# BOB_v1_04.net
KiCad netlist of a schematic drawn in EAGLE
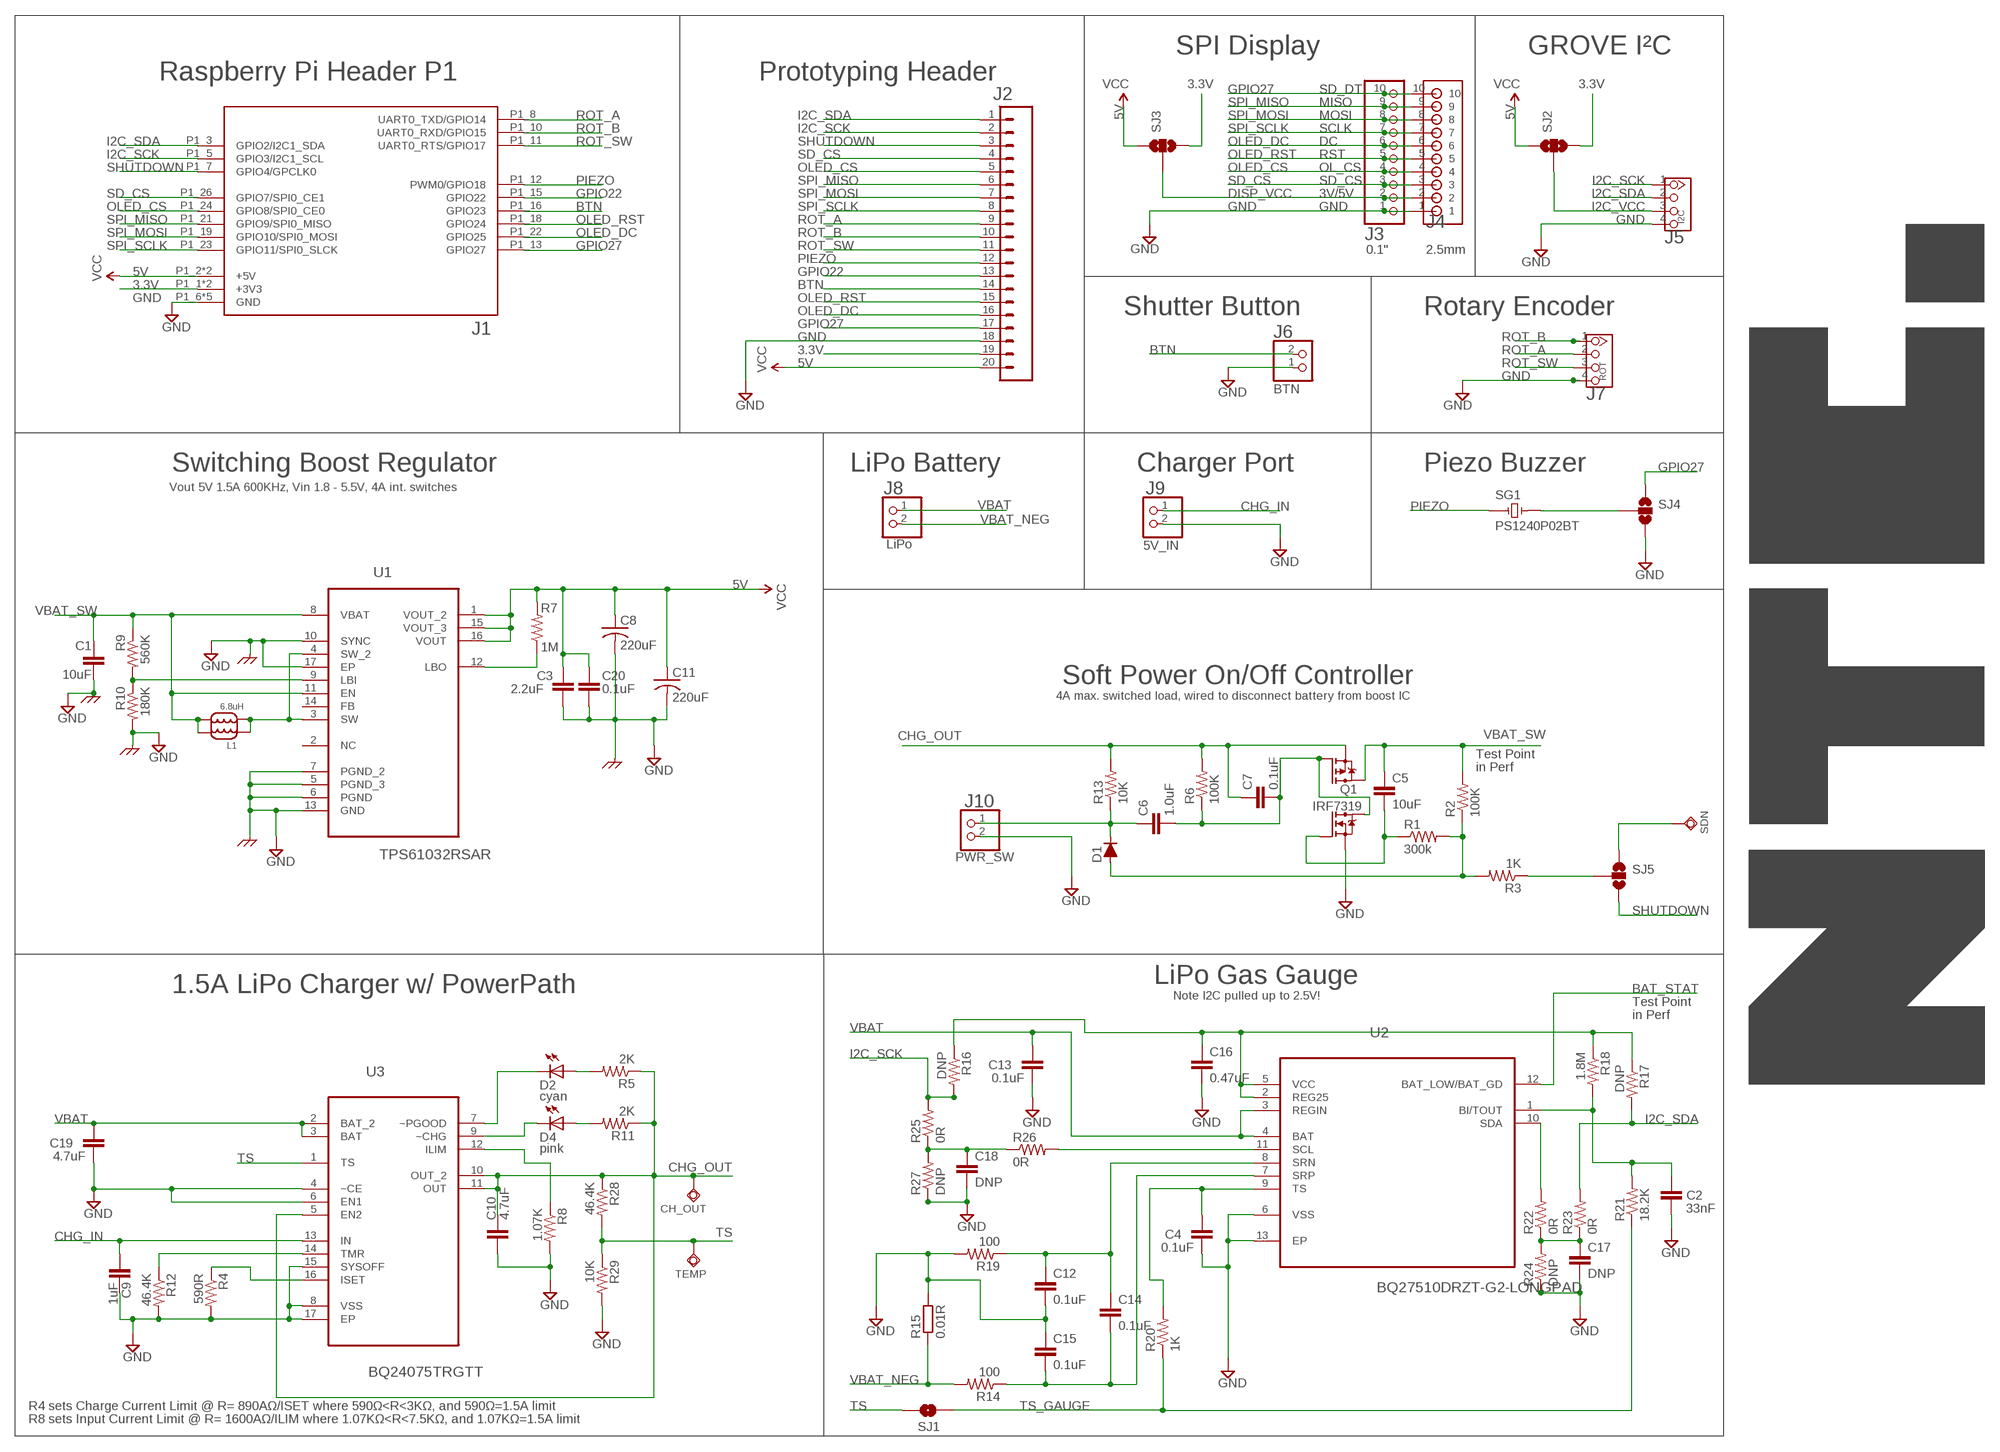
[diagram p0: schematic, sheet 1]

(export (version "E")
  (design (tool "Eeschema 10.0.6"))
  (components
    (comp (ref "C1")
      (value "10uF")
      (footprint "eagle-import:1206")
      (libsource (lib "eagle-import") (part "CAP1206"))
    )
    (comp (ref "C2")
      (value "33nF")
      (footprint "eagle-import:0603-CAP")
      (libsource (lib "eagle-import") (part "CAP0603-CAP"))
    )
    (comp (ref "C3")
      (value "2.2uF")
      (footprint "eagle-import:0603")
      (libsource (lib "eagle-import") (part "CAP0603"))
    )
    (comp (ref "C4")
      (value "0.1uF")
      (footprint "eagle-import:0603-CAP")
      (libsource (lib "eagle-import") (part "CAP0603-CAP"))
    )
    (comp (ref "C5")
      (value "10uF")
      (footprint "eagle-import:0603-CAP")
      (libsource (lib "eagle-import") (part "10UF-6.3V-20%(0603)"))
    )
    (comp (ref "C6")
      (value "1.0uF")
      (footprint "eagle-import:0603-CAP")
      (libsource (lib "eagle-import") (part "1.0UF-16V-10%(0603)"))
    )
    (comp (ref "C7")
      (value "0.1uF")
      (footprint "eagle-import:0603-CAP")
      (libsource (lib "eagle-import") (part "0.1UF-25V-5%(0603)"))
    )
    (comp (ref "C8")
      (value "220uF")
      (footprint "eagle-import:C1210")
      (libsource (lib "eagle-import") (part "C-USC1210"))
    )
    (comp (ref "C9")
      (value "1uF")
      (footprint "eagle-import:0603-CAP")
      (libsource (lib "eagle-import") (part "CAP0603-CAP"))
    )
    (comp (ref "C10")
      (value "4.7uF")
      (footprint "eagle-import:0603-CAP")
      (libsource (lib "eagle-import") (part "CAP0603-CAP"))
    )
    (comp (ref "C11")
      (value "220uF")
      (footprint "eagle-import:C1210")
      (libsource (lib "eagle-import") (part "C-USC1210"))
    )
    (comp (ref "C12")
      (value "0.1uF")
      (footprint "eagle-import:0603-CAP")
      (libsource (lib "eagle-import") (part "SparkFun-Capacitors_CAP0603-CAP"))
    )
    (comp (ref "C13")
      (value "0.1uF")
      (footprint "eagle-import:0603-CAP")
      (libsource (lib "eagle-import") (part "CAP0603-CAP"))
    )
    (comp (ref "C14")
      (value "0.1uF")
      (footprint "eagle-import:0603-CAP")
      (libsource (lib "eagle-import") (part "SparkFun-Capacitors_CAP0603-CAP"))
    )
    (comp (ref "C15")
      (value "0.1uF")
      (footprint "eagle-import:0603-CAP")
      (libsource (lib "eagle-import") (part "SparkFun-Capacitors_CAP0603-CAP"))
    )
    (comp (ref "C16")
      (value "0.47uF")
      (footprint "eagle-import:0603-CAP")
      (libsource (lib "eagle-import") (part "SparkFun-Capacitors_CAP0603-CAP"))
    )
    (comp (ref "C17")
      (value "DNP")
      (footprint "eagle-import:0603-CAP")
      (libsource (lib "eagle-import") (part "SparkFun-Capacitors_CAP0603-CAP"))
    )
    (comp (ref "C18")
      (value "DNP")
      (footprint "eagle-import:0603-CAP")
      (libsource (lib "eagle-import") (part "SparkFun-Capacitors_CAP0603-CAP"))
    )
    (comp (ref "C19")
      (value "4.7uF")
      (footprint "eagle-import:0603-CAP")
      (libsource (lib "eagle-import") (part "CAP0603-CAP"))
    )
    (comp (ref "C20")
      (value "0.1uF")
      (footprint "eagle-import:0603-CAP")
      (fields (field (name "PROD_ID") "CAP-00868"))
      (libsource (lib "eagle-import") (part "1.0UF-16V-10%(0603)"))
    )
    (comp (ref "CH_OUT")
      (value "TP1.2")
      (footprint "eagle-import:TP_1.2")
      (libsource (lib "eagle-import") (part "TP1.2"))
    )
    (comp (ref "D1")
      (value "D-FILL-SMB")
      (footprint "eagle-import:SMB")
      (libsource (lib "eagle-import") (part "D-FILL-SMB"))
    )
    (comp (ref "D2")
      (value "cyan")
      (footprint "eagle-import:LED-0603")
      (libsource (lib "eagle-import") (part "LED0603"))
    )
    (comp (ref "D4")
      (value "pink")
      (footprint "eagle-import:LED-0603")
      (libsource (lib "eagle-import") (part "LED0603"))
    )
    (comp (ref "J1")
      (value "PICAM_RPI-B-PICAM")
      (footprint "eagle-import:PICAM_RPI-B-PICAM")
      (libsource (lib "eagle-import") (part "PICAM_RPI-B-PICAM"))
    )
    (comp (ref "J2")
      (value "M20LOCK_LONGPADS")
      (footprint "eagle-import:1X20_LOCK_LONGPADS")
      (libsource (lib "eagle-import") (part "M20LOCK_LONGPADS"))
    )
    (comp (ref "J3")
      (value "PINHD-1X10")
      (footprint "eagle-import:1X10-BIG")
      (libsource (lib "eagle-import") (part "PINHD-1X10"))
    )
    (comp (ref "J4")
      (value "B10B-EH-A-RA")
      (footprint "eagle-import:S10B-EH")
      (libsource (lib "eagle-import") (part "B10B-EH-A-RA"))
    )
    (comp (ref "J5")
      (value "I2C")
      (footprint "eagle-import:CONNECTOR_4P-2.0-REVGND")
      (libsource (lib "eagle-import") (part "CONNECTOR_TWIG-4P-2.0"))
    )
    (comp (ref "J6")
      (value "BTN")
      (footprint "eagle-import:JST-PH-2-THM-REVGND")
      (libsource (lib "eagle-import") (part "JST_2PIN"))
    )
    (comp (ref "J7")
      (value "ROT")
      (footprint "eagle-import:CONNECTOR_4P-2.0-REVGND")
      (libsource (lib "eagle-import") (part "CONNECTOR_TWIG-4P-2.0"))
    )
    (comp (ref "J8")
      (value "LiPo")
      (footprint "eagle-import:PICAM_JST-PH-2-THM")
      (libsource (lib "eagle-import") (part "PICAM_JST_2PIN-THM"))
    )
    (comp (ref "J9")
      (value "5V_IN")
      (footprint "eagle-import:PICAM_JST-PH-2-THM")
      (libsource (lib "eagle-import") (part "PICAM_JST_2PIN-THM"))
    )
    (comp (ref "J10")
      (value "PWR_SW")
      (footprint "eagle-import:PICAM_JST-PH-2-THM")
      (libsource (lib "eagle-import") (part "PICAM_JST_2PIN-THM"))
    )
    (comp (ref "L1")
      (value "6.8uH")
      (footprint "eagle-import:SUMIDA_CDRH124")
      (libsource (lib "eagle-import") (part "SUMIDA_CDRH124CDRH124NP-6R8MC"))
    )
    (comp (ref "Q1")
      (value "IRF7319")
      (footprint "eagle-import:SO08-IRF")
      (libsource (lib "eagle-import") (part "IRF7319Q"))
    )
    (comp (ref "R1")
      (value "300k")
      (footprint "eagle-import:0603-RES")
      (libsource (lib "eagle-import") (part "SparkFun-Passives_RESISTOR0603-RES"))
    )
    (comp (ref "R2")
      (value "100K")
      (footprint "eagle-import:0603-RES")
      (libsource (lib "eagle-import") (part "SparkFun-Passives_RESISTOR0603-RES"))
    )
    (comp (ref "R3")
      (value "1K")
      (footprint "eagle-import:0603-RES")
      (libsource (lib "eagle-import") (part "SparkFun-Passives_RESISTOR0603-RES"))
    )
    (comp (ref "R4")
      (value "590R")
      (footprint "eagle-import:0603-RES")
      (libsource (lib "eagle-import") (part "RESISTOR0603-RES"))
    )
    (comp (ref "R5")
      (value "2K")
      (footprint "eagle-import:0603-RES")
      (libsource (lib "eagle-import") (part "RESISTOR0603-RES"))
    )
    (comp (ref "R6")
      (value "100K")
      (footprint "eagle-import:0603-RES")
      (libsource (lib "eagle-import") (part "SparkFun-Passives_RESISTOR0603-RES"))
    )
    (comp (ref "R7")
      (value "1M")
      (footprint "eagle-import:0603-RES")
      (libsource (lib "eagle-import") (part "RESISTOR0603-RES"))
    )
    (comp (ref "R8")
      (value "1.07K")
      (footprint "eagle-import:0603-RES")
      (libsource (lib "eagle-import") (part "RESISTOR0603-RES"))
    )
    (comp (ref "R9")
      (value "560K")
      (footprint "eagle-import:0603-RES")
      (libsource (lib "eagle-import") (part "RESISTOR0603-RES"))
    )
    (comp (ref "R10")
      (value "180K")
      (footprint "eagle-import:0603-RES")
      (libsource (lib "eagle-import") (part "RESISTOR0603-RES"))
    )
    (comp (ref "R11")
      (value "2K")
      (footprint "eagle-import:0603-RES")
      (libsource (lib "eagle-import") (part "RESISTOR0603-RES"))
    )
    (comp (ref "R12")
      (value "46.4K")
      (footprint "eagle-import:0603-RES")
      (libsource (lib "eagle-import") (part "RESISTOR0603-RES"))
    )
    (comp (ref "R13")
      (value "10K")
      (footprint "eagle-import:0603-RES")
      (libsource (lib "eagle-import") (part "SparkFun-Passives_RESISTOR0603-RES"))
    )
    (comp (ref "R14")
      (value "100")
      (footprint "eagle-import:0603-RES")
      (libsource (lib "eagle-import") (part "RESISTOR0603-RES"))
    )
    (comp (ref "R15")
      (value "0.01R")
      (footprint "eagle-import:R1206")
      (libsource (lib "eagle-import") (part "RESISTOR-1206"))
    )
    (comp (ref "R16")
      (value "DNP")
      (footprint "eagle-import:0603-RES")
      (libsource (lib "eagle-import") (part "RESISTOR0603-RES"))
    )
    (comp (ref "R17")
      (value "DNP")
      (footprint "eagle-import:0603-RES")
      (libsource (lib "eagle-import") (part "RESISTOR0603-RES"))
    )
    (comp (ref "R18")
      (value "1.8M")
      (footprint "eagle-import:0603-RES")
      (libsource (lib "eagle-import") (part "RESISTOR0603-RES"))
    )
    (comp (ref "R19")
      (value "100")
      (footprint "eagle-import:0603-RES")
      (libsource (lib "eagle-import") (part "RESISTOR0603-RES"))
    )
    (comp (ref "R20")
      (value "1K")
      (footprint "eagle-import:0603-RES")
      (libsource (lib "eagle-import") (part "SparkFun-Resistors_RESISTOR0603-RES"))
    )
    (comp (ref "R21")
      (value "18.2K")
      (footprint "eagle-import:0603-RES")
      (libsource (lib "eagle-import") (part "SparkFun-Resistors_RESISTOR0603-RES"))
    )
    (comp (ref "R22")
      (value "0R")
      (footprint "eagle-import:0603-RES")
      (libsource (lib "eagle-import") (part "SparkFun-Resistors_RESISTOR0603-RES"))
    )
    (comp (ref "R23")
      (value "0R")
      (footprint "eagle-import:0603-RES")
      (libsource (lib "eagle-import") (part "SparkFun-Resistors_RESISTOR0603-RES"))
    )
    (comp (ref "R24")
      (value "DNP")
      (footprint "eagle-import:0603-RES")
      (libsource (lib "eagle-import") (part "SparkFun-Resistors_RESISTOR0603-RES"))
    )
    (comp (ref "R25")
      (value "0R")
      (footprint "eagle-import:0603-RES")
      (libsource (lib "eagle-import") (part "SparkFun-Resistors_RESISTOR0603-RES"))
    )
    (comp (ref "R26")
      (value "0R")
      (footprint "eagle-import:0603-RES")
      (libsource (lib "eagle-import") (part "SparkFun-Resistors_RESISTOR0603-RES"))
    )
    (comp (ref "R27")
      (value "DNP")
      (footprint "eagle-import:0603-RES")
      (libsource (lib "eagle-import") (part "SparkFun-Resistors_RESISTOR0603-RES"))
    )
    (comp (ref "R28")
      (value "46.4K")
      (footprint "eagle-import:0603-RES")
      (libsource (lib "eagle-import") (part "RESISTOR0603-RES"))
    )
    (comp (ref "R29")
      (value "10K")
      (footprint "eagle-import:0603-RES")
      (libsource (lib "eagle-import") (part "RESISTOR0603-RES"))
    )
    (comp (ref "SDN")
      (value "TP1.2")
      (footprint "eagle-import:TP_1.2")
      (libsource (lib "eagle-import") (part "TP1.2"))
    )
    (comp (ref "SG1")
      (value "PS1240P02BT")
      (footprint "eagle-import:PS1240")
      (libsource (lib "eagle-import") (part "PS1240P02BT"))
    )
    (comp (ref "SJ1")
      (value "SOLDERJUMPER-OLDTRACE")
      (footprint "eagle-import:SJ_2S-TRACE")
      (libsource (lib "eagle-import") (part "SOLDERJUMPER-OLDTRACE"))
    )
    (comp (ref "SJ2")
      (value "SOLDERJUMPER_2WAYPASTE1&2")
      (footprint "eagle-import:SJ_3_PASTE1&2")
      (libsource (lib "eagle-import") (part "SOLDERJUMPER_2WAYPASTE1&2"))
    )
    (comp (ref "SJ3")
      (value "SOLDERJUMPER_2WAYPASTE2&3")
      (footprint "eagle-import:SJ_3_PASTE2&3")
      (libsource (lib "eagle-import") (part "SOLDERJUMPER_2WAYPASTE2&3"))
    )
    (comp (ref "SJ4")
      (value "SOLDERJUMPER_2WAYPASTE1&2")
      (footprint "eagle-import:SJ_3_PASTE1&2")
      (libsource (lib "eagle-import") (part "SOLDERJUMPER_2WAYPASTE1&2"))
    )
    (comp (ref "SJ5")
      (value "SOLDERJUMPER_2WAYPASTE2&3")
      (footprint "eagle-import:SJ_3_PASTE2&3")
      (libsource (lib "eagle-import") (part "SOLDERJUMPER_2WAYPASTE2&3"))
    )
    (comp (ref "TEMP")
      (value "TP1.2")
      (footprint "eagle-import:TP_1.2")
      (libsource (lib "eagle-import") (part "TP1.2"))
    )
    (comp (ref "U1")
      (value "TPS61032RSAR")
      (footprint "eagle-import:QFN65P400X400X100-17N")
      (libsource (lib "eagle-import") (part "TPS61032RSAR"))
    )
    (comp (ref "U2")
      (value "BQ27510DRZT-G2-LONGPAD")
      (footprint "eagle-import:SON40P400X250X100-13N+LONGPAD")
      (fields (field (name "MPN") "BQ27510DRZT-G2") (field (name "SUPPLIER") "Texas Inustruments"))
      (libsource (lib "eagle-import") (part "BQ27510DRZT-G2-LONGPAD"))
    )
    (comp (ref "U3")
      (value "BQ24075TRGTT")
      (footprint "eagle-import:QFN50P300X300X100-17N")
      (libsource (lib "eagle-import") (part "BQ24075TRGTT"))
    )
  )
  (nets
    (net (code "1") (name "3.3V") (class "Default")
      (node (ref "J1") (pin "P1_1") (pinfunction "+3V3_P1_1") (pintype "power_in"))
      (node (ref "J1") (pin "P1_17") (pinfunction "+3V3_P1_17") (pintype "power_in"))
      (node (ref "J2") (pin "19") (pinfunction "19_19") (pintype "passive"))
      (node (ref "SJ2") (pin "3") (pinfunction "3_3") (pintype "passive"))
      (node (ref "SJ3") (pin "3") (pinfunction "3_3") (pintype "passive"))
    )
    (net (code "2") (name "5V") (class "Default")
      (node (ref "C11") (pin "1") (pinfunction "1_1") (pintype "passive"))
      (node (ref "C20") (pin "1") (pinfunction "1_1") (pintype "passive"))
      (node (ref "C3") (pin "1") (pinfunction "1_1") (pintype "passive"))
      (node (ref "C8") (pin "1") (pinfunction "1_1") (pintype "passive"))
      (node (ref "J1") (pin "P1_2") (pinfunction "+5V_P1_2") (pintype "power_in"))
      (node (ref "J1") (pin "P1_4") (pinfunction "+5V_P1_4") (pintype "power_in"))
      (node (ref "J2") (pin "20") (pinfunction "20_20") (pintype "passive"))
      (node (ref "R7") (pin "2") (pinfunction "2_2") (pintype "passive"))
      (node (ref "SJ2") (pin "1") (pinfunction "1_1") (pintype "passive"))
      (node (ref "SJ3") (pin "1") (pinfunction "1_1") (pintype "passive"))
      (node (ref "U1") (pin "1") (pinfunction "VOUT_2_1") (pintype "output"))
      (node (ref "U1") (pin "15") (pinfunction "VOUT_3_15") (pintype "output"))
      (node (ref "U1") (pin "16") (pinfunction "VOUT_16") (pintype "output"))
    )
    (net (code "3") (name "BAT_STAT") (class "Default")
      (node (ref "U2") (pin "12") (pinfunction "BAT_LOW/BAT_GD_12") (pintype "output"))
    )
    (net (code "4") (name "BTN") (class "Default")
      (node (ref "J1") (pin "P1_16") (pinfunction "GPIO23_P1_16") (pintype "bidirectional"))
      (node (ref "J2") (pin "14") (pinfunction "14_14") (pintype "passive"))
      (node (ref "J6") (pin "2") (pinfunction "1_2") (pintype "passive"))
    )
    (net (code "5") (name "CHG_IN") (class "Default")
      (node (ref "C9") (pin "1") (pinfunction "1_1") (pintype "passive"))
      (node (ref "J9") (pin "1") (pinfunction "2_1") (pintype "passive"))
      (node (ref "U3") (pin "13") (pinfunction "IN_13") (pintype "input"))
    )
    (net (code "6") (name "CHG_OUT") (class "Default")
      (node (ref "C10") (pin "1") (pinfunction "1_1") (pintype "passive"))
      (node (ref "C7") (pin "1") (pinfunction "1_1") (pintype "passive"))
      (node (ref "CH_OUT") (pin "1") (pinfunction "TP_1") (pintype "passive"))
      (node (ref "Q1") (pin "3") (pinfunction "P-S2_3") (pintype "passive"))
      (node (ref "R11") (pin "1") (pinfunction "1_1") (pintype "passive"))
      (node (ref "R13") (pin "2") (pinfunction "2_2") (pintype "passive"))
      (node (ref "R28") (pin "1") (pinfunction "1_1") (pintype "passive"))
      (node (ref "R5") (pin "1") (pinfunction "1_1") (pintype "passive"))
      (node (ref "R6") (pin "2") (pinfunction "2_2") (pintype "passive"))
      (node (ref "U3") (pin "10") (pinfunction "OUT_2_10") (pintype "output"))
      (node (ref "U3") (pin "11") (pinfunction "OUT_11") (pintype "output"))
      (node (ref "U3") (pin "5") (pinfunction "EN2_5") (pintype "input"))
    )
    (net (code "7") (name "DISP_VCC") (class "Default")
      (node (ref "J3") (pin "2") (pinfunction "2_2") (pintype "passive"))
      (node (ref "J4") (pin "2") (pinfunction "2_2") (pintype "bidirectional"))
      (node (ref "SJ3") (pin "2") (pinfunction "2_2") (pintype "passive"))
    )
    (net (code "8") (name "GND") (class "Default")
      (node (ref "C1") (pin "2") (pinfunction "2_2") (pintype "passive"))
      (node (ref "C10") (pin "2") (pinfunction "2_2") (pintype "passive"))
      (node (ref "C11") (pin "2") (pinfunction "2_2") (pintype "passive"))
      (node (ref "C12") (pin "2") (pinfunction "2_2") (pintype "passive"))
      (node (ref "C13") (pin "2") (pinfunction "2_2") (pintype "passive"))
      (node (ref "C15") (pin "1") (pinfunction "1_1") (pintype "passive"))
      (node (ref "C16") (pin "2") (pinfunction "2_2") (pintype "passive"))
      (node (ref "C17") (pin "2") (pinfunction "2_2") (pintype "passive"))
      (node (ref "C18") (pin "2") (pinfunction "2_2") (pintype "passive"))
      (node (ref "C19") (pin "2") (pinfunction "2_2") (pintype "passive"))
      (node (ref "C2") (pin "2") (pinfunction "2_2") (pintype "passive"))
      (node (ref "C20") (pin "2") (pinfunction "2_2") (pintype "passive"))
      (node (ref "C3") (pin "2") (pinfunction "2_2") (pintype "passive"))
      (node (ref "C4") (pin "2") (pinfunction "2_2") (pintype "passive"))
      (node (ref "C8") (pin "2") (pinfunction "2_2") (pintype "passive"))
      (node (ref "C9") (pin "2") (pinfunction "2_2") (pintype "passive"))
      (node (ref "J1") (pin "P1_14") (pinfunction "GND_P1_14") (pintype "power_in"))
      (node (ref "J1") (pin "P1_20") (pinfunction "GND_P1_20") (pintype "power_in"))
      (node (ref "J1") (pin "P1_25") (pinfunction "GND_P1_25") (pintype "power_in"))
      (node (ref "J1") (pin "P1_6") (pinfunction "GND_P1_6") (pintype "power_in"))
      (node (ref "J1") (pin "P1_9") (pinfunction "GND_P1_9") (pintype "power_in"))
      (node (ref "J10") (pin "2") (pinfunction "1_2") (pintype "passive"))
      (node (ref "J2") (pin "18") (pinfunction "18_18") (pintype "passive"))
      (node (ref "J3") (pin "1") (pinfunction "1_1") (pintype "passive"))
      (node (ref "J4") (pin "1") (pinfunction "1_1") (pintype "bidirectional"))
      (node (ref "J5") (pin "4") (pinfunction "4_4") (pintype "bidirectional"))
      (node (ref "J6") (pin "1") (pinfunction "2_1") (pintype "passive"))
      (node (ref "J7") (pin "4") (pinfunction "4_4") (pintype "bidirectional"))
      (node (ref "J9") (pin "2") (pinfunction "1_2") (pintype "passive"))
      (node (ref "Q1") (pin "1") (pinfunction "N-S1_1") (pintype "passive"))
      (node (ref "R10") (pin "2") (pinfunction "2_2") (pintype "passive"))
      (node (ref "R12") (pin "2") (pinfunction "2_2") (pintype "passive"))
      (node (ref "R15") (pin "2") (pinfunction "2_2") (pintype "passive"))
      (node (ref "R19") (pin "2") (pinfunction "2_2") (pintype "passive"))
      (node (ref "R24") (pin "1") (pinfunction "1_1") (pintype "passive"))
      (node (ref "R27") (pin "1") (pinfunction "1_1") (pintype "passive"))
      (node (ref "R29") (pin "2") (pinfunction "2_2") (pintype "passive"))
      (node (ref "R4") (pin "2") (pinfunction "2_2") (pintype "passive"))
      (node (ref "R8") (pin "2") (pinfunction "2_2") (pintype "passive"))
      (node (ref "SJ4") (pin "3") (pinfunction "3_3") (pintype "passive"))
      (node (ref "U1") (pin "10") (pinfunction "SYNC_10") (pintype "input"))
      (node (ref "U1") (pin "13") (pinfunction "GND_13") (pintype "passive"))
      (node (ref "U1") (pin "17") (pinfunction "EP_17") (pintype "passive"))
      (node (ref "U1") (pin "5") (pinfunction "PGND_3_5") (pintype "passive"))
      (node (ref "U1") (pin "6") (pinfunction "PGND_6") (pintype "passive"))
      (node (ref "U1") (pin "7") (pinfunction "PGND_2_7") (pintype "passive"))
      (node (ref "U2") (pin "13") (pinfunction "EP_13") (pintype "passive"))
      (node (ref "U2") (pin "6") (pinfunction "VSS_6") (pintype "power_in"))
      (node (ref "U3") (pin "15") (pinfunction "SYSOFF_15") (pintype "input"))
      (node (ref "U3") (pin "17") (pinfunction "EP_17") (pintype "passive"))
      (node (ref "U3") (pin "4") (pinfunction "~{CE}_4") (pintype "input"))
      (node (ref "U3") (pin "6") (pinfunction "EN1_6") (pintype "input"))
      (node (ref "U3") (pin "8") (pinfunction "VSS_8") (pintype "passive"))
    )
    (net (code "9") (name "GPIO22") (class "Default")
      (node (ref "J1") (pin "P1_15") (pinfunction "GPIO22_P1_15") (pintype "bidirectional"))
      (node (ref "J2") (pin "13") (pinfunction "13_13") (pintype "passive"))
    )
    (net (code "10") (name "GPIO27") (class "Default")
      (node (ref "J1") (pin "P1_13") (pinfunction "GPIO27_P1_13") (pintype "bidirectional"))
      (node (ref "J2") (pin "17") (pinfunction "17_17") (pintype "passive"))
      (node (ref "J3") (pin "10") (pinfunction "10_10") (pintype "passive"))
      (node (ref "J4") (pin "10") (pinfunction "10_10") (pintype "bidirectional"))
      (node (ref "SJ4") (pin "1") (pinfunction "1_1") (pintype "passive"))
    )
    (net (code "11") (name "I2C_SCK") (class "Default")
      (node (ref "J1") (pin "P1_5") (pinfunction "GPIO3/I2C1_SCL_P1_5") (pintype "bidirectional"))
      (node (ref "J2") (pin "2") (pinfunction "2_2") (pintype "passive"))
      (node (ref "J5") (pin "1") (pinfunction "1_1") (pintype "bidirectional"))
      (node (ref "R16") (pin "2") (pinfunction "2_2") (pintype "passive"))
      (node (ref "R25") (pin "2") (pinfunction "2_2") (pintype "passive"))
    )
    (net (code "12") (name "I2C_SDA") (class "Default")
      (node (ref "J1") (pin "P1_3") (pinfunction "GPIO2/I2C1_SDA_P1_3") (pintype "bidirectional"))
      (node (ref "J2") (pin "1") (pinfunction "1_1") (pintype "passive"))
      (node (ref "J5") (pin "2") (pinfunction "2_2") (pintype "bidirectional"))
      (node (ref "R17") (pin "2") (pinfunction "2_2") (pintype "passive"))
      (node (ref "R23") (pin "2") (pinfunction "2_2") (pintype "passive"))
    )
    (net (code "13") (name "I2C_VCC") (class "Default")
      (node (ref "J5") (pin "3") (pinfunction "3_3") (pintype "bidirectional"))
      (node (ref "SJ2") (pin "2") (pinfunction "2_2") (pintype "passive"))
    )
    (net (code "14") (name "Net-(C17-Pad1)") (class "Default")
      (node (ref "C17") (pin "1") (pinfunction "1_1") (pintype "passive"))
      (node (ref "R22") (pin "1") (pinfunction "1_1") (pintype "passive"))
      (node (ref "R23") (pin "1") (pinfunction "1_1") (pintype "passive"))
      (node (ref "R24") (pin "2") (pinfunction "2_2") (pintype "passive"))
    )
    (net (code "15") (name "Net-(C18-Pad1)") (class "Default")
      (node (ref "C18") (pin "1") (pinfunction "1_1") (pintype "passive"))
      (node (ref "R25") (pin "1") (pinfunction "1_1") (pintype "passive"))
      (node (ref "R26") (pin "1") (pinfunction "1_1") (pintype "passive"))
      (node (ref "R27") (pin "2") (pinfunction "2_2") (pintype "passive"))
    )
    (net (code "16") (name "Net-(D1-A)") (class "Default")
      (node (ref "D1") (pin "2") (pinfunction "A_2") (pintype "passive"))
      (node (ref "R1") (pin "2") (pinfunction "2_2") (pintype "passive"))
      (node (ref "R2") (pin "1") (pinfunction "1_1") (pintype "passive"))
      (node (ref "R3") (pin "2") (pinfunction "2_2") (pintype "passive"))
    )
    (net (code "17") (name "Net-(D1-C)") (class "Default")
      (node (ref "C6") (pin "1") (pinfunction "1_1") (pintype "passive"))
      (node (ref "D1") (pin "1") (pinfunction "C_1") (pintype "passive"))
      (node (ref "J10") (pin "1") (pinfunction "2_1") (pintype "passive"))
      (node (ref "R13") (pin "1") (pinfunction "1_1") (pintype "passive"))
    )
    (net (code "18") (name "Net-(D2-PadA)") (class "Default")
      (node (ref "D2") (pin "A") (pinfunction "A_A") (pintype "passive"))
      (node (ref "R5") (pin "2") (pinfunction "2_2") (pintype "passive"))
    )
    (net (code "19") (name "Net-(D4-PadA)") (class "Default")
      (node (ref "D4") (pin "A") (pinfunction "A_A") (pintype "passive"))
      (node (ref "R11") (pin "2") (pinfunction "2_2") (pintype "passive"))
    )
    (net (code "20") (name "Net-(Q1-N-G1)") (class "Default")
      (node (ref "C5") (pin "2") (pinfunction "2_2") (pintype "passive"))
      (node (ref "Q1") (pin "2") (pinfunction "N-G1_2") (pintype "passive"))
      (node (ref "R1") (pin "1") (pinfunction "1_1") (pintype "passive"))
    )
    (net (code "21") (name "Net-(Q1-P-G2)") (class "Default")
      (node (ref "C6") (pin "2") (pinfunction "2_2") (pintype "passive"))
      (node (ref "C7") (pin "2") (pinfunction "2_2") (pintype "passive"))
      (node (ref "Q1") (pin "4") (pinfunction "P-G2_4") (pintype "passive"))
      (node (ref "Q1") (pin "7") (pinfunction "N-D1_7") (pintype "passive"))
      (node (ref "Q1") (pin "8") (pinfunction "N-D1_8") (pintype "passive"))
      (node (ref "R6") (pin "1") (pinfunction "1_1") (pintype "passive"))
    )
    (net (code "22") (name "Net-(R3-Pad1)") (class "Default")
      (node (ref "R3") (pin "1") (pinfunction "1_1") (pintype "passive"))
      (node (ref "SJ5") (pin "2") (pinfunction "2_2") (pintype "passive"))
    )
    (net (code "23") (name "Net-(SDN-TP)") (class "Default")
      (node (ref "SDN") (pin "1") (pinfunction "TP_1") (pintype "passive"))
      (node (ref "SJ5") (pin "1") (pinfunction "1_1") (pintype "passive"))
    )
    (net (code "24") (name "Net-(SG1-2)") (class "Default")
      (node (ref "SG1") (pin "P$2") (pinfunction "2_P$2") (pintype "passive"))
      (node (ref "SJ4") (pin "2") (pinfunction "2_2") (pintype "passive"))
    )
    (net (code "25") (name "Net-(U1-LBI)") (class "Default")
      (node (ref "R10") (pin "1") (pinfunction "1_1") (pintype "passive"))
      (node (ref "R9") (pin "2") (pinfunction "2_2") (pintype "passive"))
      (node (ref "U1") (pin "9") (pinfunction "LBI_9") (pintype "input"))
    )
    (net (code "26") (name "Net-(U1-LBO)") (class "Default")
      (node (ref "R7") (pin "1") (pinfunction "1_1") (pintype "passive"))
      (node (ref "U1") (pin "12") (pinfunction "LBO_12") (pintype "output"))
    )
    (net (code "27") (name "Net-(U1-SW)") (class "Default")
      (node (ref "L1") (pin "P$3") (pinfunction "2_P$3") (pintype "passive"))
      (node (ref "L1") (pin "P$4") (pinfunction "2_P$4") (pintype "passive"))
      (node (ref "U1") (pin "3") (pinfunction "SW_3") (pintype "input"))
      (node (ref "U1") (pin "4") (pinfunction "SW_2_4") (pintype "input"))
    )
    (net (code "28") (name "Net-(U2-BI{slash}TOUT)") (class "Default")
      (node (ref "C2") (pin "1") (pinfunction "1_1") (pintype "passive"))
      (node (ref "R18") (pin "2") (pinfunction "2_2") (pintype "passive"))
      (node (ref "R21") (pin "2") (pinfunction "2_2") (pintype "passive"))
      (node (ref "U2") (pin "1") (pinfunction "BI/TOUT_1") (pintype "bidirectional"))
    )
    (net (code "29") (name "Net-(U2-REG25)") (class "Default")
      (node (ref "C16") (pin "1") (pinfunction "1_1") (pintype "passive"))
      (node (ref "R16") (pin "1") (pinfunction "1_1") (pintype "passive"))
      (node (ref "R17") (pin "1") (pinfunction "1_1") (pintype "passive"))
      (node (ref "R18") (pin "1") (pinfunction "1_1") (pintype "passive"))
      (node (ref "U2") (pin "2") (pinfunction "REG25_2") (pintype "power_in"))
      (node (ref "U2") (pin "5") (pinfunction "VCC_5") (pintype "power_in"))
    )
    (net (code "30") (name "Net-(U2-SCL)") (class "Default")
      (node (ref "R26") (pin "2") (pinfunction "2_2") (pintype "passive"))
      (node (ref "U2") (pin "11") (pinfunction "SCL_11") (pintype "input"))
    )
    (net (code "31") (name "Net-(U2-SDA)") (class "Default")
      (node (ref "R22") (pin "2") (pinfunction "2_2") (pintype "passive"))
      (node (ref "U2") (pin "10") (pinfunction "SDA_10") (pintype "bidirectional"))
    )
    (net (code "32") (name "Net-(U2-SRN)") (class "Default")
      (node (ref "C12") (pin "1") (pinfunction "1_1") (pintype "passive"))
      (node (ref "C14") (pin "1") (pinfunction "1_1") (pintype "passive"))
      (node (ref "R19") (pin "1") (pinfunction "1_1") (pintype "passive"))
      (node (ref "U2") (pin "8") (pinfunction "SRN_8") (pintype "input"))
    )
    (net (code "33") (name "Net-(U2-SRP)") (class "Default")
      (node (ref "C14") (pin "2") (pinfunction "2_2") (pintype "passive"))
      (node (ref "C15") (pin "2") (pinfunction "2_2") (pintype "passive"))
      (node (ref "R14") (pin "1") (pinfunction "1_1") (pintype "passive"))
      (node (ref "U2") (pin "7") (pinfunction "SRP_7") (pintype "input"))
    )
    (net (code "34") (name "Net-(U2-TS)") (class "Default")
      (node (ref "C4") (pin "1") (pinfunction "1_1") (pintype "passive"))
      (node (ref "R20") (pin "2") (pinfunction "2_2") (pintype "passive"))
      (node (ref "U2") (pin "9") (pinfunction "TS_9") (pintype "input"))
    )
    (net (code "35") (name "Net-(U3-ILIM)") (class "Default")
      (node (ref "R8") (pin "1") (pinfunction "1_1") (pintype "passive"))
      (node (ref "U3") (pin "12") (pinfunction "ILIM_12") (pintype "output"))
    )
    (net (code "36") (name "Net-(U3-ISET)") (class "Default")
      (node (ref "R4") (pin "1") (pinfunction "1_1") (pintype "passive"))
      (node (ref "U3") (pin "16") (pinfunction "ISET_16") (pintype "bidirectional"))
    )
    (net (code "37") (name "Net-(U3-TMR)") (class "Default")
      (node (ref "R12") (pin "1") (pinfunction "1_1") (pintype "passive"))
      (node (ref "U3") (pin "14") (pinfunction "TMR_14") (pintype "input"))
    )
    (net (code "38") (name "Net-(U3-~{CHG})") (class "Default")
      (node (ref "D4") (pin "C") (pinfunction "C_C") (pintype "passive"))
      (node (ref "U3") (pin "9") (pinfunction "~{CHG}_9") (pintype "output"))
    )
    (net (code "39") (name "Net-(U3-~{PGOOD})") (class "Default")
      (node (ref "D2") (pin "C") (pinfunction "C_C") (pintype "passive"))
      (node (ref "U3") (pin "7") (pinfunction "~{PGOOD}_7") (pintype "output"))
    )
    (net (code "40") (name "OLED_CS") (class "Default")
      (node (ref "J1") (pin "P1_24") (pinfunction "GPIO8/SPI0_CE0_P1_24") (pintype "bidirectional"))
      (node (ref "J2") (pin "5") (pinfunction "5_5") (pintype "passive"))
      (node (ref "J3") (pin "4") (pinfunction "4_4") (pintype "passive"))
      (node (ref "J4") (pin "4") (pinfunction "4_4") (pintype "bidirectional"))
    )
    (net (code "41") (name "OLED_DC") (class "Default")
      (node (ref "J1") (pin "P1_22") (pinfunction "GPIO25_P1_22") (pintype "bidirectional"))
      (node (ref "J2") (pin "16") (pinfunction "16_16") (pintype "passive"))
      (node (ref "J3") (pin "6") (pinfunction "6_6") (pintype "passive"))
      (node (ref "J4") (pin "6") (pinfunction "6_6") (pintype "bidirectional"))
    )
    (net (code "42") (name "OLED_RST") (class "Default")
      (node (ref "J1") (pin "P1_18") (pinfunction "GPIO24_P1_18") (pintype "bidirectional"))
      (node (ref "J2") (pin "15") (pinfunction "15_15") (pintype "passive"))
      (node (ref "J3") (pin "5") (pinfunction "5_5") (pintype "passive"))
      (node (ref "J4") (pin "5") (pinfunction "5_5") (pintype "bidirectional"))
    )
    (net (code "43") (name "PIEZO") (class "Default")
      (node (ref "J1") (pin "P1_12") (pinfunction "PWM0/GPIO18_P1_12") (pintype "bidirectional"))
      (node (ref "J2") (pin "12") (pinfunction "12_12") (pintype "passive"))
      (node (ref "SG1") (pin "P$1") (pinfunction "1_P$1") (pintype "passive"))
    )
    (net (code "44") (name "ROT_A") (class "Default")
      (node (ref "J1") (pin "P1_8") (pinfunction "UART0_TXD/GPIO14_P1_8") (pintype "bidirectional"))
      (node (ref "J2") (pin "9") (pinfunction "9_9") (pintype "passive"))
      (node (ref "J7") (pin "2") (pinfunction "2_2") (pintype "bidirectional"))
    )
    (net (code "45") (name "ROT_B") (class "Default")
      (node (ref "J1") (pin "P1_10") (pinfunction "UART0_RXD/GPIO15_P1_10") (pintype "bidirectional"))
      (node (ref "J2") (pin "10") (pinfunction "10_10") (pintype "passive"))
      (node (ref "J7") (pin "1") (pinfunction "1_1") (pintype "bidirectional"))
    )
    (net (code "46") (name "ROT_SW") (class "Default")
      (node (ref "J1") (pin "P1_11") (pinfunction "UART0_RTS/GPIO17_P1_11") (pintype "bidirectional"))
      (node (ref "J2") (pin "11") (pinfunction "11_11") (pintype "passive"))
      (node (ref "J7") (pin "3") (pinfunction "3_3") (pintype "bidirectional"))
    )
    (net (code "47") (name "SD_CS") (class "Default")
      (node (ref "J1") (pin "P1_26") (pinfunction "GPIO7/SPI0_CE1_P1_26") (pintype "bidirectional"))
      (node (ref "J2") (pin "4") (pinfunction "4_4") (pintype "passive"))
      (node (ref "J3") (pin "3") (pinfunction "3_3") (pintype "passive"))
      (node (ref "J4") (pin "3") (pinfunction "3_3") (pintype "bidirectional"))
    )
    (net (code "48") (name "SHUTDOWN") (class "Default")
      (node (ref "J1") (pin "P1_7") (pinfunction "GPIO4/GPCLK0_P1_7") (pintype "bidirectional"))
      (node (ref "J2") (pin "3") (pinfunction "3_3") (pintype "passive"))
      (node (ref "SJ5") (pin "3") (pinfunction "3_3") (pintype "passive"))
    )
    (net (code "49") (name "SPI_MISO") (class "Default")
      (node (ref "J1") (pin "P1_21") (pinfunction "GPIO9/SPI0_MISO_P1_21") (pintype "bidirectional"))
      (node (ref "J2") (pin "6") (pinfunction "6_6") (pintype "passive"))
      (node (ref "J3") (pin "9") (pinfunction "9_9") (pintype "passive"))
      (node (ref "J4") (pin "9") (pinfunction "9_9") (pintype "bidirectional"))
    )
    (net (code "50") (name "SPI_MOSI") (class "Default")
      (node (ref "J1") (pin "P1_19") (pinfunction "GPIO10/SPI0_MOSI_P1_19") (pintype "bidirectional"))
      (node (ref "J2") (pin "7") (pinfunction "7_7") (pintype "passive"))
      (node (ref "J3") (pin "8") (pinfunction "8_8") (pintype "passive"))
      (node (ref "J4") (pin "8") (pinfunction "8_8") (pintype "bidirectional"))
    )
    (net (code "51") (name "SPI_SCLK") (class "Default")
      (node (ref "J1") (pin "P1_23") (pinfunction "GPIO11/SPI0_SLCK_P1_23") (pintype "bidirectional"))
      (node (ref "J2") (pin "8") (pinfunction "8_8") (pintype "passive"))
      (node (ref "J3") (pin "7") (pinfunction "7_7") (pintype "passive"))
      (node (ref "J4") (pin "7") (pinfunction "7_7") (pintype "bidirectional"))
    )
    (net (code "52") (name "TS") (class "Default")
      (node (ref "R28") (pin "2") (pinfunction "2_2") (pintype "passive"))
      (node (ref "R29") (pin "1") (pinfunction "1_1") (pintype "passive"))
      (node (ref "SJ1") (pin "1") (pinfunction "1_1") (pintype "passive"))
      (node (ref "TEMP") (pin "1") (pinfunction "TP_1") (pintype "passive"))
      (node (ref "U3") (pin "1") (pinfunction "TS_1") (pintype "bidirectional"))
    )
    (net (code "53") (name "TS_GAUGE") (class "Default")
      (node (ref "R20") (pin "1") (pinfunction "1_1") (pintype "passive"))
      (node (ref "R21") (pin "1") (pinfunction "1_1") (pintype "passive"))
      (node (ref "SJ1") (pin "2") (pinfunction "2_2") (pintype "passive"))
    )
    (net (code "54") (name "VBAT") (class "Default")
      (node (ref "C13") (pin "1") (pinfunction "1_1") (pintype "passive"))
      (node (ref "C19") (pin "1") (pinfunction "1_1") (pintype "passive"))
      (node (ref "J8") (pin "1") (pinfunction "2_1") (pintype "passive"))
      (node (ref "U2") (pin "3") (pinfunction "REGIN_3") (pintype "power_in"))
      (node (ref "U2") (pin "4") (pinfunction "BAT_4") (pintype "input"))
      (node (ref "U3") (pin "2") (pinfunction "BAT_2_2") (pintype "bidirectional"))
      (node (ref "U3") (pin "3") (pinfunction "BAT_3") (pintype "bidirectional"))
    )
    (net (code "55") (name "VBAT_NEG") (class "Default")
      (node (ref "J8") (pin "2") (pinfunction "1_2") (pintype "passive"))
      (node (ref "R14") (pin "2") (pinfunction "2_2") (pintype "passive"))
      (node (ref "R15") (pin "1") (pinfunction "1_1") (pintype "passive"))
    )
    (net (code "56") (name "VBAT_SW") (class "Default")
      (node (ref "C1") (pin "1") (pinfunction "1_1") (pintype "passive"))
      (node (ref "C5") (pin "1") (pinfunction "1_1") (pintype "passive"))
      (node (ref "L1") (pin "P$1") (pinfunction "1_P$1") (pintype "passive"))
      (node (ref "L1") (pin "P$2") (pinfunction "1_P$2") (pintype "passive"))
      (node (ref "Q1") (pin "5") (pinfunction "P-D2_5") (pintype "passive"))
      (node (ref "Q1") (pin "6") (pinfunction "P-D2_6") (pintype "passive"))
      (node (ref "R2") (pin "2") (pinfunction "2_2") (pintype "passive"))
      (node (ref "R9") (pin "1") (pinfunction "1_1") (pintype "passive"))
      (node (ref "U1") (pin "11") (pinfunction "EN_11") (pintype "input"))
      (node (ref "U1") (pin "8") (pinfunction "VBAT_8") (pintype "input"))
    )
    (net (code "57") (name "unconnected-(U1-FB-Pad14)") (class "Default")
      (node (ref "U1") (pin "14") (pinfunction "FB_14") (pintype "input"))
    )
    (net (code "58") (name "unconnected-(U1-NC-Pad2)") (class "Default")
      (node (ref "U1") (pin "2") (pinfunction "NC_2") (pintype "no_connect"))
    )
  )
)
